# 06-Lightsensor.net
KiCad netlist of a schematic drawn in Altium Designer
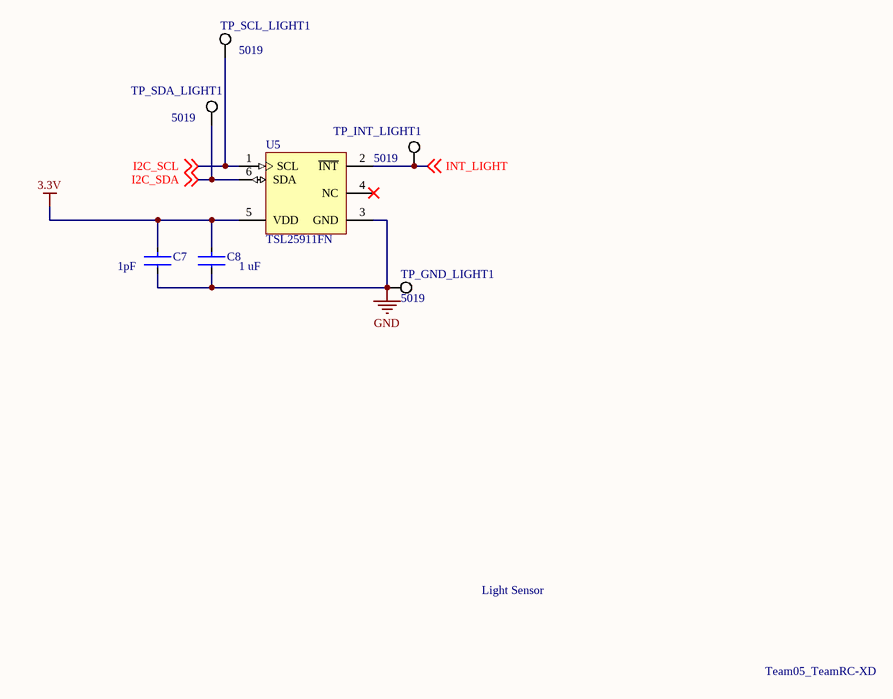
[diagram p0: 06-Lightsensor.SchDoc]

(export (version "E")
  (design (tool "Eeschema 10.0.6"))
  (components
    (comp (ref "C7")
      (value "CC0805BRNPO9BN1R0")
      (footprint "FP-CC0805-0_1-0_7-IPC_B")
      (description "CAP CER 1PF 50V C0G/NPO 0805")
      (fields (field (name "CAPACITANCE") "1pF") (field (name "MANUFACTURER") "Yageo"))
      (libsource (lib "Altium Content Vault") (part "b4654b650e69147ec39a6b967a45e02"))
    )
    (comp (ref "C8")
      (value "1 uF")
      (footprint "FP-CC0805-0_85-MFG")
      (description "CAP CER 1UF 10V X7R 0805")
      (fields
        (field (name "MANUFACTURER") "Yageo")
        (field (name "OCTOPART") "https://octopart.com/cc0805kkx7r6bb105-yageo-42522859")
      )
      (libsource (lib "Altium Content Vault") (part "11868f565c42a9108669ba33697ecf6"))
    )
    (comp (ref "TP_GND_LIGHT1")
      (value "5019")
      (footprint "KSTN-5019_V")
      (description "Test Point, 1 Position SMD, RoHS, Tape and Reel")
      (fields (field (name "MANUFACTURER") "Keystone Electronics"))
      (libsource (lib "Altium Content Vault") (part "TESTPOINT_WHITE"))
    )
    (comp (ref "TP_INT_LIGHT1")
      (value "5019")
      (footprint "KSTN-5019_V")
      (description "Test Point, 1 Position SMD, RoHS, Tape and Reel")
      (fields (field (name "MANUFACTURER") "Keystone Electronics"))
      (libsource (lib "Altium Content Vault") (part "TESTPOINT_WHITE"))
    )
    (comp (ref "TP_SCL_LIGHT1")
      (value "5019")
      (footprint "KSTN-5019_V")
      (description "Test Point, 1 Position SMD, RoHS, Tape and Reel")
      (fields (field (name "MANUFACTURER") "Keystone Electronics"))
      (libsource (lib "Altium Content Vault") (part "TESTPOINT_WHITE"))
    )
    (comp (ref "TP_SDA_LIGHT1")
      (value "5019")
      (footprint "KSTN-5019_V")
      (description "Test Point, 1 Position SMD, RoHS, Tape and Reel")
      (fields (field (name "MANUFACTURER") "Keystone Electronics"))
      (libsource (lib "Altium Content Vault") (part "TESTPOINT_WHITE"))
    )
    (comp (ref "U5")
      (value "TSL25911FN")
      (footprint "AMS-FN-6-2400X2000DE_V")
      (description "Light-to-Digital Converter with I2C Interface, 2.7 to 3.6 V, -30 to 70 degC, FN-6, Pb-Free, Reel")
      (fields (field (name "MANUFACTURER") "AMS"))
      (libsource (lib "Altium Content Vault") (part "AMS-TSL25911-FN-6"))
    )
  )
  (nets
    (net (code "1") (name "3.3V") (class "Default")
      (node (ref "C7") (pin "1") (pinfunction "1_1") (pintype "passive"))
      (node (ref "C8") (pin "1") (pinfunction "1_1") (pintype "passive"))
      (node (ref "U5") (pin "5") (pinfunction "VDD_5") (pintype "power_in"))
    )
    (net (code "2") (name "GND") (class "Default")
      (node (ref "C7") (pin "2") (pinfunction "2_2") (pintype "passive"))
      (node (ref "C8") (pin "2") (pinfunction "2_2") (pintype "passive"))
      (node (ref "TP_GND_LIGHT1") (pin "1") (pinfunction "1_1") (pintype "passive"))
      (node (ref "U5") (pin "3") (pinfunction "GND_3") (pintype "power_in"))
    )
    (net (code "3") (name "I2C_SCL") (class "Default")
      (node (ref "TP_SCL_LIGHT1") (pin "1") (pinfunction "1_1") (pintype "passive"))
      (node (ref "U5") (pin "1") (pinfunction "SCL_1") (pintype "input"))
    )
    (net (code "4") (name "I2C_SDA") (class "Default")
      (node (ref "TP_SDA_LIGHT1") (pin "1") (pinfunction "1_1") (pintype "passive"))
      (node (ref "U5") (pin "6") (pinfunction "SDA_6") (pintype "bidirectional"))
    )
    (net (code "5") (name "INT_LIGHT") (class "Default")
      (node (ref "TP_INT_LIGHT1") (pin "1") (pinfunction "1_1") (pintype "passive"))
      (node (ref "U5") (pin "2") (pinfunction "~{INT}_2") (pintype "open_collector"))
    )
    (net (code "6") (name "unconnected-(U5-NC-Pad4)") (class "Default")
      (node (ref "U5") (pin "4") (pinfunction "NC_4") (pintype "passive+no_connect"))
    )
  )
)
